# SCH_Neo_geo_chip_adapter_2026-08-27.net
KiCad netlist of a schematic drawn in EasyEDA
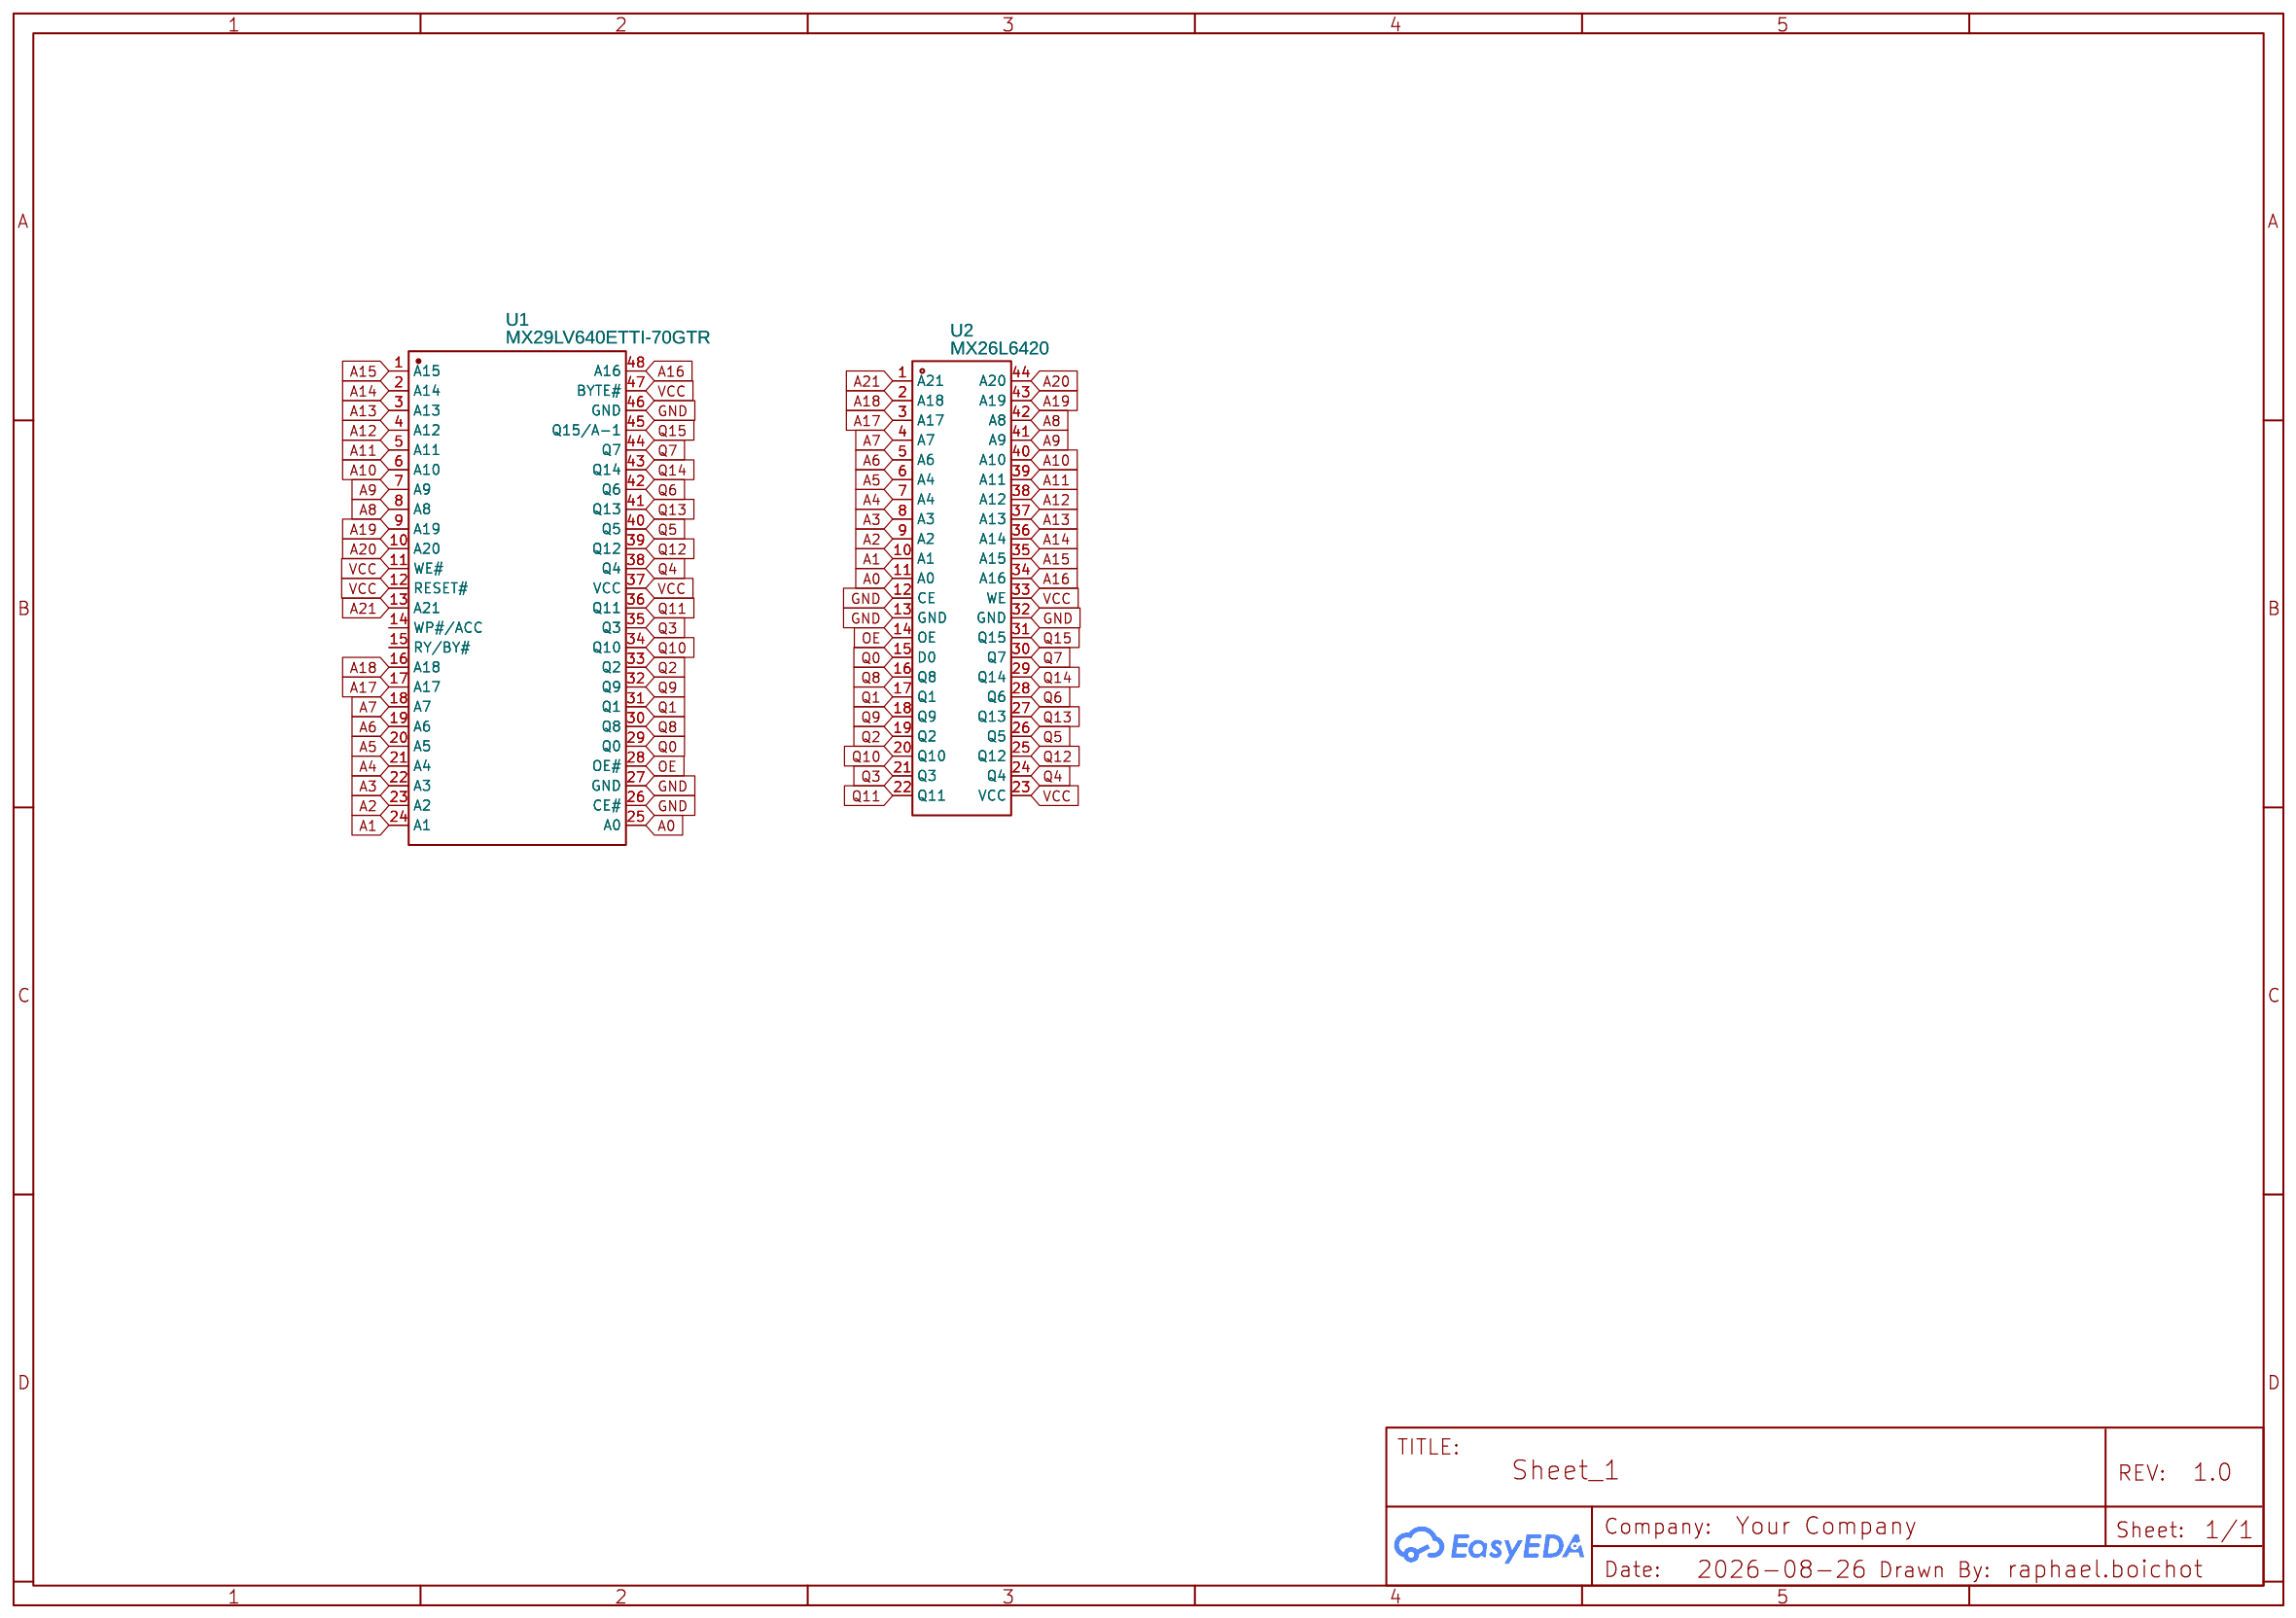
[diagram p0: schematic sheet]

(export (version "E")
  (design (tool "Eeschema 10.0.6"))
  (components
    (comp (ref "U1")
      (value "MX29LV640ETTI-70GTR")
      (fields (field (name "Manufacturer") "MXIC(旺宏电子)"))
      (libsource (lib "") (part "MX29LV640ETTI-70GTR"))
    )
    (comp (ref "U2")
      (value "MX26L6420")
      (fields (field (name "Manufacturer") "Macronix"))
      (libsource (lib "") (part "MX26L6420"))
    )
  )
  (nets
    (net (code "1") (name "A0") (class "Default")
      (node (ref "U1") (pin "25") (pinfunction "A0_25") (pintype "unspecified"))
      (node (ref "U2") (pin "11") (pinfunction "A0_11") (pintype "unspecified"))
    )
    (net (code "2") (name "A1") (class "Default")
      (node (ref "U1") (pin "24") (pinfunction "A1_24") (pintype "unspecified"))
      (node (ref "U2") (pin "10") (pinfunction "A1_10") (pintype "unspecified"))
    )
    (net (code "3") (name "A2") (class "Default")
      (node (ref "U1") (pin "23") (pinfunction "A2_23") (pintype "unspecified"))
      (node (ref "U2") (pin "9") (pinfunction "A2_9") (pintype "unspecified"))
    )
    (net (code "4") (name "A3") (class "Default")
      (node (ref "U1") (pin "22") (pinfunction "A3_22") (pintype "unspecified"))
      (node (ref "U2") (pin "8") (pinfunction "A3_8") (pintype "unspecified"))
    )
    (net (code "5") (name "A4") (class "Default")
      (node (ref "U1") (pin "21") (pinfunction "A4_21") (pintype "unspecified"))
      (node (ref "U2") (pin "7") (pinfunction "A4_7") (pintype "unspecified"))
    )
    (net (code "6") (name "A5") (class "Default")
      (node (ref "U1") (pin "20") (pinfunction "A5_20") (pintype "unspecified"))
      (node (ref "U2") (pin "6") (pinfunction "A4_6") (pintype "unspecified"))
    )
    (net (code "7") (name "A6") (class "Default")
      (node (ref "U1") (pin "19") (pinfunction "A6_19") (pintype "unspecified"))
      (node (ref "U2") (pin "5") (pinfunction "A6_5") (pintype "unspecified"))
    )
    (net (code "8") (name "A7") (class "Default")
      (node (ref "U1") (pin "18") (pinfunction "A7_18") (pintype "unspecified"))
      (node (ref "U2") (pin "4") (pinfunction "A7_4") (pintype "unspecified"))
    )
    (net (code "9") (name "A8") (class "Default")
      (node (ref "U1") (pin "8") (pinfunction "A8_8") (pintype "unspecified"))
      (node (ref "U2") (pin "42") (pinfunction "A8_42") (pintype "unspecified"))
    )
    (net (code "10") (name "A9") (class "Default")
      (node (ref "U1") (pin "7") (pinfunction "A9_7") (pintype "unspecified"))
      (node (ref "U2") (pin "41") (pinfunction "A9_41") (pintype "unspecified"))
    )
    (net (code "11") (name "A10") (class "Default")
      (node (ref "U1") (pin "6") (pinfunction "A10_6") (pintype "unspecified"))
      (node (ref "U2") (pin "40") (pinfunction "A10_40") (pintype "unspecified"))
    )
    (net (code "12") (name "A11") (class "Default")
      (node (ref "U1") (pin "5") (pinfunction "A11_5") (pintype "unspecified"))
      (node (ref "U2") (pin "39") (pinfunction "A11_39") (pintype "unspecified"))
    )
    (net (code "13") (name "A12") (class "Default")
      (node (ref "U1") (pin "4") (pinfunction "A12_4") (pintype "unspecified"))
      (node (ref "U2") (pin "38") (pinfunction "A12_38") (pintype "unspecified"))
    )
    (net (code "14") (name "A13") (class "Default")
      (node (ref "U1") (pin "3") (pinfunction "A13_3") (pintype "unspecified"))
      (node (ref "U2") (pin "37") (pinfunction "A13_37") (pintype "unspecified"))
    )
    (net (code "15") (name "A14") (class "Default")
      (node (ref "U1") (pin "2") (pinfunction "A14_2") (pintype "unspecified"))
      (node (ref "U2") (pin "36") (pinfunction "A14_36") (pintype "unspecified"))
    )
    (net (code "16") (name "A15") (class "Default")
      (node (ref "U1") (pin "1") (pinfunction "A15_1") (pintype "unspecified"))
      (node (ref "U2") (pin "35") (pinfunction "A15_35") (pintype "unspecified"))
    )
    (net (code "17") (name "A16") (class "Default")
      (node (ref "U1") (pin "48") (pinfunction "A16_48") (pintype "unspecified"))
      (node (ref "U2") (pin "34") (pinfunction "A16_34") (pintype "unspecified"))
    )
    (net (code "18") (name "A17") (class "Default")
      (node (ref "U1") (pin "17") (pinfunction "A17_17") (pintype "unspecified"))
      (node (ref "U2") (pin "3") (pinfunction "A17_3") (pintype "unspecified"))
    )
    (net (code "19") (name "A18") (class "Default")
      (node (ref "U1") (pin "16") (pinfunction "A18_16") (pintype "unspecified"))
      (node (ref "U2") (pin "2") (pinfunction "A18_2") (pintype "unspecified"))
    )
    (net (code "20") (name "A19") (class "Default")
      (node (ref "U1") (pin "9") (pinfunction "A19_9") (pintype "unspecified"))
      (node (ref "U2") (pin "43") (pinfunction "A19_43") (pintype "unspecified"))
    )
    (net (code "21") (name "A20") (class "Default")
      (node (ref "U1") (pin "10") (pinfunction "A20_10") (pintype "unspecified"))
      (node (ref "U2") (pin "44") (pinfunction "A20_44") (pintype "unspecified"))
    )
    (net (code "22") (name "A21") (class "Default")
      (node (ref "U1") (pin "13") (pinfunction "A21_13") (pintype "unspecified"))
      (node (ref "U2") (pin "1") (pinfunction "A21_1") (pintype "unspecified"))
    )
    (net (code "23") (name "GND") (class "Default")
      (node (ref "U1") (pin "26") (pinfunction "CE#_26") (pintype "unspecified"))
      (node (ref "U1") (pin "27") (pinfunction "GND_27") (pintype "unspecified"))
      (node (ref "U1") (pin "46") (pinfunction "GND_46") (pintype "unspecified"))
      (node (ref "U2") (pin "12") (pinfunction "CE_12") (pintype "unspecified"))
      (node (ref "U2") (pin "13") (pinfunction "GND_13") (pintype "unspecified"))
      (node (ref "U2") (pin "32") (pinfunction "GND_32") (pintype "unspecified"))
    )
    (net (code "24") (name "OE") (class "Default")
      (node (ref "U1") (pin "28") (pinfunction "OE#_28") (pintype "unspecified"))
      (node (ref "U2") (pin "14") (pinfunction "OE_14") (pintype "unspecified"))
    )
    (net (code "25") (name "Q0") (class "Default")
      (node (ref "U1") (pin "29") (pinfunction "Q0_29") (pintype "unspecified"))
      (node (ref "U2") (pin "15") (pinfunction "D0_15") (pintype "unspecified"))
    )
    (net (code "26") (name "Q1") (class "Default")
      (node (ref "U1") (pin "31") (pinfunction "Q1_31") (pintype "unspecified"))
      (node (ref "U2") (pin "17") (pinfunction "Q1_17") (pintype "unspecified"))
    )
    (net (code "27") (name "Q2") (class "Default")
      (node (ref "U1") (pin "33") (pinfunction "Q2_33") (pintype "unspecified"))
      (node (ref "U2") (pin "19") (pinfunction "Q2_19") (pintype "unspecified"))
    )
    (net (code "28") (name "Q3") (class "Default")
      (node (ref "U1") (pin "35") (pinfunction "Q3_35") (pintype "unspecified"))
      (node (ref "U2") (pin "21") (pinfunction "Q3_21") (pintype "unspecified"))
    )
    (net (code "29") (name "Q4") (class "Default")
      (node (ref "U1") (pin "38") (pinfunction "Q4_38") (pintype "unspecified"))
      (node (ref "U2") (pin "24") (pinfunction "Q4_24") (pintype "unspecified"))
    )
    (net (code "30") (name "Q5") (class "Default")
      (node (ref "U1") (pin "40") (pinfunction "Q5_40") (pintype "unspecified"))
      (node (ref "U2") (pin "26") (pinfunction "Q5_26") (pintype "unspecified"))
    )
    (net (code "31") (name "Q6") (class "Default")
      (node (ref "U1") (pin "42") (pinfunction "Q6_42") (pintype "unspecified"))
      (node (ref "U2") (pin "28") (pinfunction "Q6_28") (pintype "unspecified"))
    )
    (net (code "32") (name "Q7") (class "Default")
      (node (ref "U1") (pin "44") (pinfunction "Q7_44") (pintype "unspecified"))
      (node (ref "U2") (pin "30") (pinfunction "Q7_30") (pintype "unspecified"))
    )
    (net (code "33") (name "Q8") (class "Default")
      (node (ref "U1") (pin "30") (pinfunction "Q8_30") (pintype "unspecified"))
      (node (ref "U2") (pin "16") (pinfunction "Q8_16") (pintype "unspecified"))
    )
    (net (code "34") (name "Q9") (class "Default")
      (node (ref "U1") (pin "32") (pinfunction "Q9_32") (pintype "unspecified"))
      (node (ref "U2") (pin "18") (pinfunction "Q9_18") (pintype "unspecified"))
    )
    (net (code "35") (name "Q10") (class "Default")
      (node (ref "U1") (pin "34") (pinfunction "Q10_34") (pintype "unspecified"))
      (node (ref "U2") (pin "20") (pinfunction "Q10_20") (pintype "unspecified"))
    )
    (net (code "36") (name "Q11") (class "Default")
      (node (ref "U1") (pin "36") (pinfunction "Q11_36") (pintype "unspecified"))
      (node (ref "U2") (pin "22") (pinfunction "Q11_22") (pintype "unspecified"))
    )
    (net (code "37") (name "Q12") (class "Default")
      (node (ref "U1") (pin "39") (pinfunction "Q12_39") (pintype "unspecified"))
      (node (ref "U2") (pin "25") (pinfunction "Q12_25") (pintype "unspecified"))
    )
    (net (code "38") (name "Q13") (class "Default")
      (node (ref "U1") (pin "41") (pinfunction "Q13_41") (pintype "unspecified"))
      (node (ref "U2") (pin "27") (pinfunction "Q13_27") (pintype "unspecified"))
    )
    (net (code "39") (name "Q14") (class "Default")
      (node (ref "U1") (pin "43") (pinfunction "Q14_43") (pintype "unspecified"))
      (node (ref "U2") (pin "29") (pinfunction "Q14_29") (pintype "unspecified"))
    )
    (net (code "40") (name "Q15") (class "Default")
      (node (ref "U1") (pin "45") (pinfunction "Q15/A-1_45") (pintype "unspecified"))
      (node (ref "U2") (pin "31") (pinfunction "Q15_31") (pintype "unspecified"))
    )
    (net (code "41") (name "VCC") (class "Default")
      (node (ref "U1") (pin "11") (pinfunction "WE#_11") (pintype "unspecified"))
      (node (ref "U1") (pin "12") (pinfunction "RESET#_12") (pintype "unspecified"))
      (node (ref "U1") (pin "37") (pinfunction "VCC_37") (pintype "unspecified"))
      (node (ref "U1") (pin "47") (pinfunction "BYTE#_47") (pintype "unspecified"))
      (node (ref "U2") (pin "23") (pinfunction "VCC_23") (pintype "unspecified"))
      (node (ref "U2") (pin "33") (pinfunction "WE_33") (pintype "unspecified"))
    )
    (net (code "42") (name "unconnected-(U1-RY{slash}BY#-Pad15)") (class "Default")
      (node (ref "U1") (pin "15") (pinfunction "RY/BY#_15") (pintype "unspecified"))
    )
    (net (code "43") (name "unconnected-(U1-WP#{slash}ACC-Pad14)") (class "Default")
      (node (ref "U1") (pin "14") (pinfunction "WP#/ACC_14") (pintype "unspecified"))
    )
  )
)
